# board.net
KiCad netlist of a schematic drawn in EAGLE
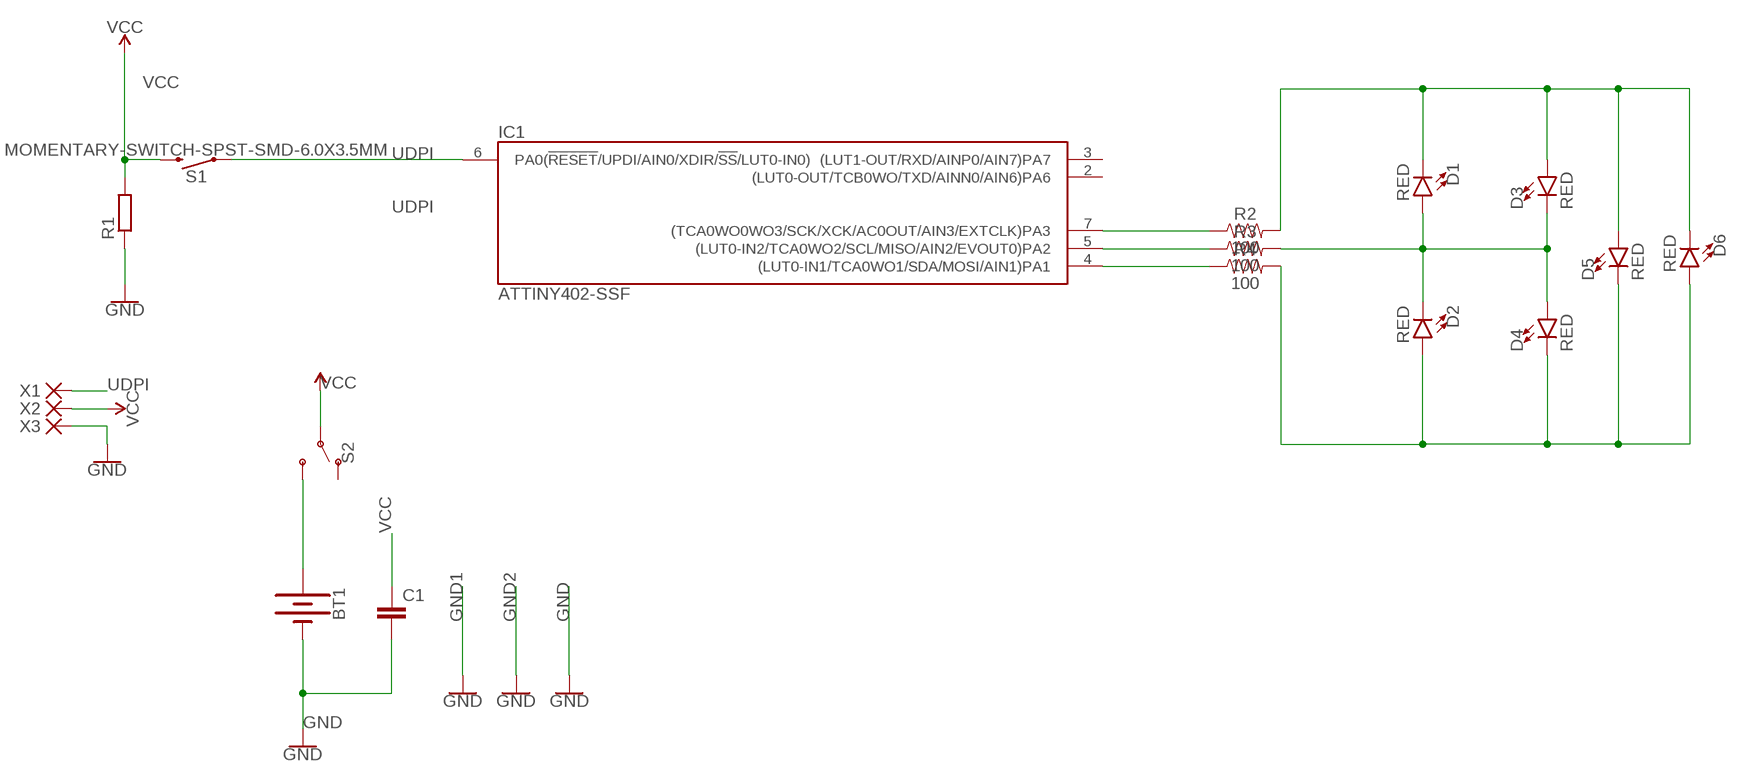
[diagram p0: schematic, sheet 1]

(export (version "E")
  (design (tool "Eeschema 10.0.6"))
  (components
    (comp (ref "BT1")
      (value "BATTERY-20MM_SMD")
      (footprint "eagle-import:BATTCON_20MM")
      (libsource (lib "eagle-import") (part "BATTERY-20MM_SMD"))
    )
    (comp (ref "C1")
      (value "C-EUC0805")
      (footprint "eagle-import:C0805")
      (libsource (lib "eagle-import") (part "C-EUC0805"))
    )
    (comp (ref "D1")
      (value "RED")
      (footprint "eagle-import:LED-0603")
      (libsource (lib "eagle-import") (part "LED-RED0603"))
    )
    (comp (ref "D2")
      (value "RED")
      (footprint "eagle-import:LED-0603")
      (libsource (lib "eagle-import") (part "LED-RED0603"))
    )
    (comp (ref "D3")
      (value "RED")
      (footprint "eagle-import:LED-0603")
      (libsource (lib "eagle-import") (part "LED-RED0603"))
    )
    (comp (ref "D4")
      (value "RED")
      (footprint "eagle-import:LED-0603")
      (libsource (lib "eagle-import") (part "LED-RED0603"))
    )
    (comp (ref "D5")
      (value "RED")
      (footprint "eagle-import:LED-0603")
      (libsource (lib "eagle-import") (part "LED-RED0603"))
    )
    (comp (ref "D6")
      (value "RED")
      (footprint "eagle-import:LED-0603")
      (libsource (lib "eagle-import") (part "LED-RED0603"))
    )
    (comp (ref "IC1")
      (value "ATTINY402-SSF")
      (footprint "eagle-import:SO8")
      (libsource (lib "eagle-import") (part "ATTINY02-SSF4"))
    )
    (comp (ref "R1")
      (value "R-EU_R0603")
      (footprint "eagle-import:R0603")
      (libsource (lib "eagle-import") (part "R-EU_R0603"))
    )
    (comp (ref "R2")
      (value "100")
      (footprint "eagle-import:0603")
      (libsource (lib "eagle-import") (part "100OHM-0603-1/10W-1%"))
    )
    (comp (ref "R3")
      (value "100")
      (footprint "eagle-import:0603")
      (libsource (lib "eagle-import") (part "100OHM-0603-1/10W-1%"))
    )
    (comp (ref "R4")
      (value "100")
      (footprint "eagle-import:0603")
      (libsource (lib "eagle-import") (part "100OHM-0603-1/10W-1%"))
    )
    (comp (ref "S1")
      (value "MOMENTARY-SWITCH-SPST-SMD-6.0X3.5MM")
      (footprint "eagle-import:TACTILE_SWITCH_SMD_6.0X3.5MM")
      (libsource (lib "eagle-import") (part "MOMENTARY-SWITCH-SPST-SMD-6.0X3.5MM"))
    )
    (comp (ref "S2")
      (value "SWITCH-SPDT-SMD-RIGHT-ANGLE")
      (footprint "eagle-import:SWITCH_SPST_SMD_A")
      (libsource (lib "eagle-import") (part "SWITCH-SPDT-SMD-RIGHT-ANGLE"))
    )
    (comp (ref "X1")
      (value "PAD-1.27X2.54")
      (footprint "eagle-import:PAD-1.27X2.54")
      (libsource (lib "eagle-import") (part "PAD-1.27X2.54"))
    )
    (comp (ref "X2")
      (value "PAD-1.27X2.54")
      (footprint "eagle-import:PAD-1.27X2.54")
      (libsource (lib "eagle-import") (part "PAD-1.27X2.54"))
    )
    (comp (ref "X3")
      (value "PAD-1.27X2.54")
      (footprint "eagle-import:PAD-1.27X2.54")
      (libsource (lib "eagle-import") (part "PAD-1.27X2.54"))
    )
  )
  (nets
    (net (code "1") (name "/UDPI") (class "Default")
      (node (ref "IC1") (pin "6") (pinfunction "PA0(~{RESET}/UPDI/AIN0/XDIR/~{SS}/LUT0-IN0)_6") (pintype "bidirectional"))
      (node (ref "S1") (pin "1") (pinfunction "1_1") (pintype "passive"))
      (node (ref "X1") (pin "1") (pinfunction "P_1") (pintype "passive"))
    )
    (net (code "2") (name "GND") (class "Default")
      (node (ref "BT1") (pin "2") (pinfunction "-_2") (pintype "power_in"))
      (node (ref "C1") (pin "2") (pinfunction "2_2") (pintype "passive"))
      (node (ref "R1") (pin "1") (pinfunction "1_1") (pintype "passive"))
      (node (ref "X3") (pin "1") (pinfunction "P_1") (pintype "passive"))
    )
    (net (code "3") (name "Net-(BT1-+)") (class "Default")
      (node (ref "BT1") (pin "1") (pinfunction "+_1") (pintype "power_in"))
      (node (ref "S2") (pin "3") (pinfunction "S_3") (pintype "passive"))
    )
    (net (code "4") (name "Net-(D1-PadA)") (class "Default")
      (node (ref "D1") (pin "A") (pinfunction "A_A") (pintype "passive"))
      (node (ref "D2") (pin "C") (pinfunction "C_C") (pintype "passive"))
      (node (ref "D3") (pin "C") (pinfunction "C_C") (pintype "passive"))
      (node (ref "D4") (pin "A") (pinfunction "A_A") (pintype "passive"))
      (node (ref "R3") (pin "2") (pinfunction "2_2") (pintype "passive"))
    )
    (net (code "5") (name "Net-(D1-PadC)") (class "Default")
      (node (ref "D1") (pin "C") (pinfunction "C_C") (pintype "passive"))
      (node (ref "D3") (pin "A") (pinfunction "A_A") (pintype "passive"))
      (node (ref "D5") (pin "A") (pinfunction "A_A") (pintype "passive"))
      (node (ref "D6") (pin "C") (pinfunction "C_C") (pintype "passive"))
      (node (ref "R2") (pin "2") (pinfunction "2_2") (pintype "passive"))
    )
    (net (code "6") (name "Net-(D2-PadA)") (class "Default")
      (node (ref "D2") (pin "A") (pinfunction "A_A") (pintype "passive"))
      (node (ref "D4") (pin "C") (pinfunction "C_C") (pintype "passive"))
      (node (ref "D5") (pin "C") (pinfunction "C_C") (pintype "passive"))
      (node (ref "D6") (pin "A") (pinfunction "A_A") (pintype "passive"))
      (node (ref "R4") (pin "2") (pinfunction "2_2") (pintype "passive"))
    )
    (net (code "7") (name "Net-(IC1A-(LUT0-IN1{slash}TCA0WO1{slash}SDA{slash}MOSI{slash}AIN1)PA1)") (class "Default")
      (node (ref "IC1") (pin "4") (pinfunction "(LUT0-IN1/TCA0WO1/SDA/MOSI/AIN1)PA1_4") (pintype "bidirectional"))
      (node (ref "R4") (pin "1") (pinfunction "1_1") (pintype "passive"))
    )
    (net (code "8") (name "Net-(IC1A-(LUT0-IN2{slash}TCA0WO2{slash}SCL{slash}MISO{slash}AIN2{slash}EVOUT0)PA2)") (class "Default")
      (node (ref "IC1") (pin "5") (pinfunction "(LUT0-IN2/TCA0WO2/SCL/MISO/AIN2/EVOUT0)PA2_5") (pintype "bidirectional"))
      (node (ref "R3") (pin "1") (pinfunction "1_1") (pintype "passive"))
    )
    (net (code "9") (name "Net-(IC1A-(TCA0WO0WO3{slash}SCK{slash}XCK{slash}AC0OUT{slash}AIN3{slash}EXTCLK)PA3)") (class "Default")
      (node (ref "IC1") (pin "7") (pinfunction "(TCA0WO0WO3/SCK/XCK/AC0OUT/AIN3/EXTCLK)PA3_7") (pintype "bidirectional"))
      (node (ref "R2") (pin "1") (pinfunction "1_1") (pintype "passive"))
    )
    (net (code "10") (name "VCC") (class "Default")
      (node (ref "C1") (pin "1") (pinfunction "1_1") (pintype "passive"))
      (node (ref "R1") (pin "2") (pinfunction "2_2") (pintype "passive"))
      (node (ref "S1") (pin "2") (pinfunction "2_2") (pintype "passive"))
      (node (ref "S2") (pin "2") (pinfunction "P_2") (pintype "passive"))
      (node (ref "X2") (pin "1") (pinfunction "P_1") (pintype "passive"))
    )
    (net (code "11") (name "unconnected-(IC1A-(LUT0-OUT{slash}TCB0WO{slash}TXD{slash}AINN0{slash}AIN6)PA6-Pad2)") (class "Default")
      (node (ref "IC1") (pin "2") (pinfunction "(LUT0-OUT/TCB0WO/TXD/AINN0/AIN6)PA6_2") (pintype "bidirectional"))
    )
    (net (code "12") (name "unconnected-(IC1A-(LUT1-OUT{slash}RXD{slash}AINP0{slash}AIN7)PA7-Pad3)") (class "Default")
      (node (ref "IC1") (pin "3") (pinfunction "(LUT1-OUT/RXD/AINP0/AIN7)PA7_3") (pintype "bidirectional"))
    )
    (net (code "13") (name "unconnected-(S2-O-Pad1)") (class "Default")
      (node (ref "S2") (pin "1") (pinfunction "O_1") (pintype "passive"))
    )
  )
)
